# logic_board_Protorype_5_4_ver3.net
KiCad netlist of a schematic drawn in EAGLE
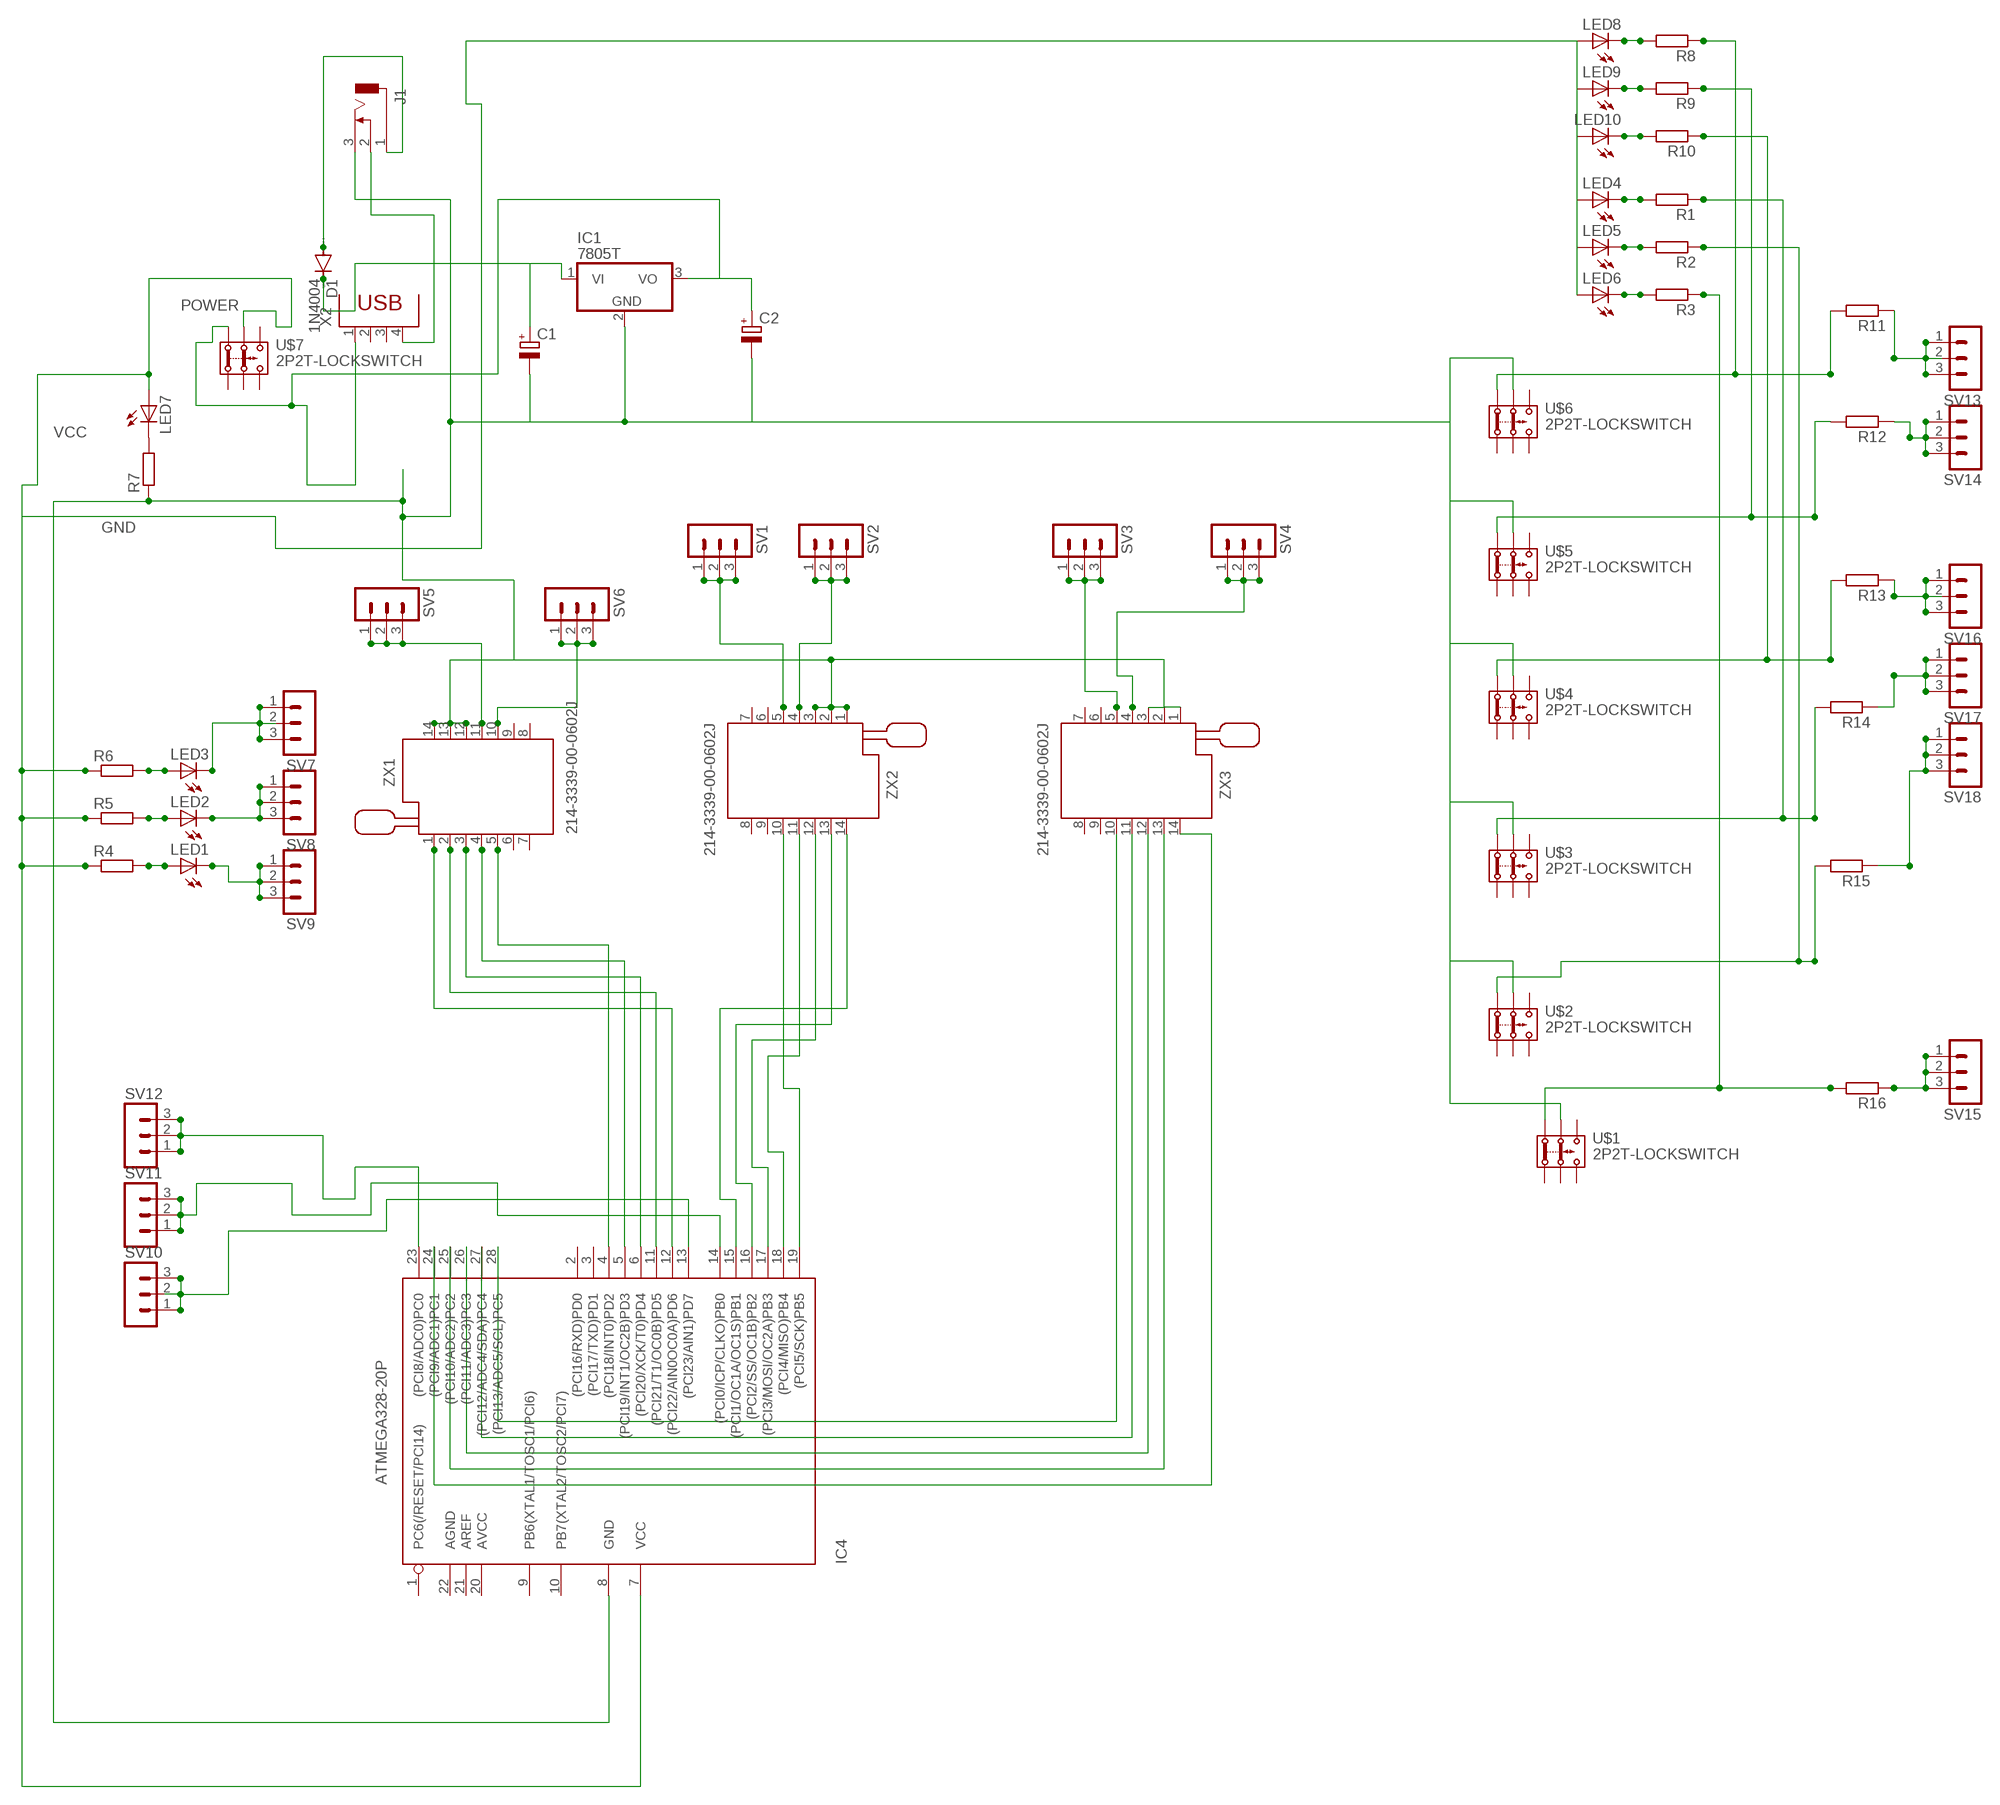
[diagram p0: schematic, sheet 1]

(export (version "E")
  (design (tool "Eeschema 10.0.6"))
  (components
    (comp (ref "C1")
      (value "CPOL-EUE2.5-6")
      (footprint "eagle-import:E2,5-6")
      (libsource (lib "eagle-import") (part "CPOL-EUE2.5-6"))
    )
    (comp (ref "C2")
      (value "CPOL-EUE2.5-6")
      (footprint "eagle-import:E2,5-6")
      (libsource (lib "eagle-import") (part "CPOL-EUE2.5-6"))
    )
    (comp (ref "D1")
      (value "1N4004")
      (footprint "eagle-import:DO41-10")
      (libsource (lib "eagle-import") (part "1N4004"))
    )
    (comp (ref "IC1")
      (value "7805T")
      (footprint "eagle-import:TO220H")
      (libsource (lib "eagle-import") (part "78T05"))
    )
    (comp (ref "IC4")
      (value "ATMEGA328-20P")
      (footprint "eagle-import:DIL28-3")
      (libsource (lib "eagle-import") (part "ATMEGA328P-20"))
    )
    (comp (ref "J1")
      (value "DCJ0303")
      (footprint "eagle-import:DCJ0303")
      (libsource (lib "eagle-import") (part "DCJ0303"))
    )
    (comp (ref "LED1")
      (value "LEDLED5MM-CHANDIMA")
      (footprint "eagle-import:LED5MM-CHANDIMA")
      (libsource (lib "eagle-import") (part "LEDLED5MM-CHANDIMA"))
    )
    (comp (ref "LED2")
      (value "LEDLED5MM-CHANDIMA")
      (footprint "eagle-import:LED5MM-CHANDIMA")
      (libsource (lib "eagle-import") (part "LEDLED5MM-CHANDIMA"))
    )
    (comp (ref "LED3")
      (value "LEDLED5MM-CHANDIMA")
      (footprint "eagle-import:LED5MM-CHANDIMA")
      (libsource (lib "eagle-import") (part "LEDLED5MM-CHANDIMA"))
    )
    (comp (ref "LED4")
      (value "LEDLED5MM-CHANDIMA")
      (footprint "eagle-import:LED5MM-CHANDIMA")
      (libsource (lib "eagle-import") (part "LEDLED5MM-CHANDIMA"))
    )
    (comp (ref "LED5")
      (value "LEDLED5MM-CHANDIMA")
      (footprint "eagle-import:LED5MM-CHANDIMA")
      (libsource (lib "eagle-import") (part "LEDLED5MM-CHANDIMA"))
    )
    (comp (ref "LED6")
      (value "LEDLED5MM-CHANDIMA")
      (footprint "eagle-import:LED5MM-CHANDIMA")
      (libsource (lib "eagle-import") (part "LEDLED5MM-CHANDIMA"))
    )
    (comp (ref "LED7")
      (value "LEDLED5MM-CHANDIMA")
      (footprint "eagle-import:LED5MM-CHANDIMA")
      (libsource (lib "eagle-import") (part "LEDLED5MM-CHANDIMA"))
    )
    (comp (ref "LED8")
      (value "LEDLED5MM-CHANDIMA")
      (footprint "eagle-import:LED5MM-CHANDIMA")
      (libsource (lib "eagle-import") (part "LEDLED5MM-CHANDIMA"))
    )
    (comp (ref "LED9")
      (value "LEDLED5MM-CHANDIMA")
      (footprint "eagle-import:LED5MM-CHANDIMA")
      (libsource (lib "eagle-import") (part "LEDLED5MM-CHANDIMA"))
    )
    (comp (ref "LED10")
      (value "LEDLED5MM-CHANDIMA")
      (footprint "eagle-import:LED5MM-CHANDIMA")
      (libsource (lib "eagle-import") (part "LEDLED5MM-CHANDIMA"))
    )
    (comp (ref "R1")
      (value "R-EU_0207/10_CHANDIMA")
      (footprint "eagle-import:0207_10_CHANDIMA")
      (libsource (lib "eagle-import") (part "R-EU_0207/10_CHANDIMA"))
    )
    (comp (ref "R2")
      (value "R-EU_0207/10_CHANDIMA")
      (footprint "eagle-import:0207_10_CHANDIMA")
      (libsource (lib "eagle-import") (part "R-EU_0207/10_CHANDIMA"))
    )
    (comp (ref "R3")
      (value "R-EU_0207/10_CHANDIMA")
      (footprint "eagle-import:0207_10_CHANDIMA")
      (libsource (lib "eagle-import") (part "R-EU_0207/10_CHANDIMA"))
    )
    (comp (ref "R4")
      (value "R-EU_0207/10_CHANDIMA")
      (footprint "eagle-import:0207_10_CHANDIMA")
      (libsource (lib "eagle-import") (part "R-EU_0207/10_CHANDIMA"))
    )
    (comp (ref "R5")
      (value "R-EU_0207/10_CHANDIMA")
      (footprint "eagle-import:0207_10_CHANDIMA")
      (libsource (lib "eagle-import") (part "R-EU_0207/10_CHANDIMA"))
    )
    (comp (ref "R6")
      (value "R-EU_0207/10_CHANDIMA")
      (footprint "eagle-import:0207_10_CHANDIMA")
      (libsource (lib "eagle-import") (part "R-EU_0207/10_CHANDIMA"))
    )
    (comp (ref "R7")
      (value "R-EU_0207/10_CHANDIMA")
      (footprint "eagle-import:0207_10_CHANDIMA")
      (libsource (lib "eagle-import") (part "R-EU_0207/10_CHANDIMA"))
    )
    (comp (ref "R8")
      (value "R-EU_0207/10_CHANDIMA")
      (footprint "eagle-import:0207_10_CHANDIMA")
      (libsource (lib "eagle-import") (part "R-EU_0207/10_CHANDIMA"))
    )
    (comp (ref "R9")
      (value "R-EU_0207/10_CHANDIMA")
      (footprint "eagle-import:0207_10_CHANDIMA")
      (libsource (lib "eagle-import") (part "R-EU_0207/10_CHANDIMA"))
    )
    (comp (ref "R10")
      (value "R-EU_0207/10_CHANDIMA")
      (footprint "eagle-import:0207_10_CHANDIMA")
      (libsource (lib "eagle-import") (part "R-EU_0207/10_CHANDIMA"))
    )
    (comp (ref "R11")
      (value "R-EU_0207/10_CHANDIMA")
      (footprint "eagle-import:0207_10_CHANDIMA")
      (libsource (lib "eagle-import") (part "R-EU_0207/10_CHANDIMA"))
    )
    (comp (ref "R12")
      (value "R-EU_0207/10_CHANDIMA")
      (footprint "eagle-import:0207_10_CHANDIMA")
      (libsource (lib "eagle-import") (part "R-EU_0207/10_CHANDIMA"))
    )
    (comp (ref "R13")
      (value "R-EU_0207/10_CHANDIMA")
      (footprint "eagle-import:0207_10_CHANDIMA")
      (libsource (lib "eagle-import") (part "R-EU_0207/10_CHANDIMA"))
    )
    (comp (ref "R14")
      (value "R-EU_0207/10_CHANDIMA")
      (footprint "eagle-import:0207_10_CHANDIMA")
      (libsource (lib "eagle-import") (part "R-EU_0207/10_CHANDIMA"))
    )
    (comp (ref "R15")
      (value "R-EU_0207/10_CHANDIMA")
      (footprint "eagle-import:0207_10_CHANDIMA")
      (libsource (lib "eagle-import") (part "R-EU_0207/10_CHANDIMA"))
    )
    (comp (ref "R16")
      (value "R-EU_0207/10_CHANDIMA")
      (footprint "eagle-import:0207_10_CHANDIMA")
      (libsource (lib "eagle-import") (part "R-EU_0207/10_CHANDIMA"))
    )
    (comp (ref "SV1")
      (value "MA03-1")
      (footprint "eagle-import:MA03-1")
      (libsource (lib "eagle-import") (part "MA03-1"))
    )
    (comp (ref "SV2")
      (value "MA03-1")
      (footprint "eagle-import:MA03-1")
      (libsource (lib "eagle-import") (part "MA03-1"))
    )
    (comp (ref "SV3")
      (value "MA03-1")
      (footprint "eagle-import:MA03-1")
      (libsource (lib "eagle-import") (part "MA03-1"))
    )
    (comp (ref "SV4")
      (value "MA03-1")
      (footprint "eagle-import:MA03-1")
      (libsource (lib "eagle-import") (part "MA03-1"))
    )
    (comp (ref "SV5")
      (value "MA03-1")
      (footprint "eagle-import:MA03-1")
      (libsource (lib "eagle-import") (part "MA03-1"))
    )
    (comp (ref "SV6")
      (value "MA03-1")
      (footprint "eagle-import:MA03-1")
      (libsource (lib "eagle-import") (part "MA03-1"))
    )
    (comp (ref "SV7")
      (value "MA03-1")
      (footprint "eagle-import:MA03-1")
      (libsource (lib "eagle-import") (part "MA03-1"))
    )
    (comp (ref "SV8")
      (value "MA03-1")
      (footprint "eagle-import:MA03-1")
      (libsource (lib "eagle-import") (part "MA03-1"))
    )
    (comp (ref "SV9")
      (value "MA03-1")
      (footprint "eagle-import:MA03-1")
      (libsource (lib "eagle-import") (part "MA03-1"))
    )
    (comp (ref "SV10")
      (value "MA03-1")
      (footprint "eagle-import:MA03-1")
      (libsource (lib "eagle-import") (part "MA03-1"))
    )
    (comp (ref "SV11")
      (value "MA03-1")
      (footprint "eagle-import:MA03-1")
      (libsource (lib "eagle-import") (part "MA03-1"))
    )
    (comp (ref "SV12")
      (value "MA03-1")
      (footprint "eagle-import:MA03-1")
      (libsource (lib "eagle-import") (part "MA03-1"))
    )
    (comp (ref "SV13")
      (value "MA03-1")
      (footprint "eagle-import:MA03-1")
      (libsource (lib "eagle-import") (part "MA03-1"))
    )
    (comp (ref "SV14")
      (value "MA03-1")
      (footprint "eagle-import:MA03-1")
      (libsource (lib "eagle-import") (part "MA03-1"))
    )
    (comp (ref "SV15")
      (value "MA03-1")
      (footprint "eagle-import:MA03-1")
      (libsource (lib "eagle-import") (part "MA03-1"))
    )
    (comp (ref "SV16")
      (value "MA03-1")
      (footprint "eagle-import:MA03-1")
      (libsource (lib "eagle-import") (part "MA03-1"))
    )
    (comp (ref "SV17")
      (value "MA03-1")
      (footprint "eagle-import:MA03-1")
      (libsource (lib "eagle-import") (part "MA03-1"))
    )
    (comp (ref "SV18")
      (value "MA03-1")
      (footprint "eagle-import:MA03-1")
      (libsource (lib "eagle-import") (part "MA03-1"))
    )
    (comp (ref "U$1")
      (value "2P2T-LOCKSWITCH")
      (footprint "eagle-import:2P2T-LOCKSWITCH")
      (libsource (lib "eagle-import") (part "2P2T-LOCKSWITCH"))
    )
    (comp (ref "U$2")
      (value "2P2T-LOCKSWITCH")
      (footprint "eagle-import:2P2T-LOCKSWITCH")
      (libsource (lib "eagle-import") (part "2P2T-LOCKSWITCH"))
    )
    (comp (ref "U$3")
      (value "2P2T-LOCKSWITCH")
      (footprint "eagle-import:2P2T-LOCKSWITCH")
      (libsource (lib "eagle-import") (part "2P2T-LOCKSWITCH"))
    )
    (comp (ref "U$4")
      (value "2P2T-LOCKSWITCH")
      (footprint "eagle-import:2P2T-LOCKSWITCH")
      (libsource (lib "eagle-import") (part "2P2T-LOCKSWITCH"))
    )
    (comp (ref "U$5")
      (value "2P2T-LOCKSWITCH")
      (footprint "eagle-import:2P2T-LOCKSWITCH")
      (libsource (lib "eagle-import") (part "2P2T-LOCKSWITCH"))
    )
    (comp (ref "U$6")
      (value "2P2T-LOCKSWITCH")
      (footprint "eagle-import:2P2T-LOCKSWITCH")
      (libsource (lib "eagle-import") (part "2P2T-LOCKSWITCH"))
    )
    (comp (ref "U$7")
      (value "2P2T-LOCKSWITCH")
      (footprint "eagle-import:2P2T-LOCKSWITCH")
      (libsource (lib "eagle-import") (part "2P2T-LOCKSWITCH"))
    )
    (comp (ref "X2")
      (value "PN61729")
      (footprint "eagle-import:PN61729")
      (libsource (lib "eagle-import") (part "PN61729"))
    )
    (comp (ref "ZX1")
      (value "214-3339-00-0602J")
      (footprint "eagle-import:214-3339-00-0602J")
      (fields (field (name "MF") "3M"))
      (libsource (lib "eagle-import") (part "214-3339-00-0602J"))
    )
    (comp (ref "ZX2")
      (value "214-3339-00-0602J")
      (footprint "eagle-import:214-3339-00-0602J")
      (fields (field (name "MF") "3M"))
      (libsource (lib "eagle-import") (part "214-3339-00-0602J"))
    )
    (comp (ref "ZX3")
      (value "214-3339-00-0602J")
      (footprint "eagle-import:214-3339-00-0602J")
      (fields (field (name "MF") "3M"))
      (libsource (lib "eagle-import") (part "214-3339-00-0602J"))
    )
  )
  (nets
    (net (code "1") (name "/GND") (class "Default")
      (node (ref "C1") (pin "-") (pinfunction "-_-") (pintype "passive"))
      (node (ref "C2") (pin "-") (pinfunction "-_-") (pintype "passive"))
      (node (ref "IC1") (pin "2") (pinfunction "GND_2") (pintype "passive"))
      (node (ref "IC4") (pin "8") (pinfunction "GND_8") (pintype "bidirectional"))
      (node (ref "J1") (pin "3") (pinfunction "3_3") (pintype "passive"))
      (node (ref "R7") (pin "1") (pinfunction "1_1") (pintype "passive"))
      (node (ref "U$1") (pin "2.1") (pinfunction "2.1_2.1") (pintype "passive"))
      (node (ref "U$2") (pin "2.1") (pinfunction "2.1_2.1") (pintype "passive"))
      (node (ref "U$3") (pin "2.1") (pinfunction "2.1_2.1") (pintype "passive"))
      (node (ref "U$4") (pin "2.1") (pinfunction "2.1_2.1") (pintype "passive"))
      (node (ref "U$5") (pin "2.1") (pinfunction "2.1_2.1") (pintype "passive"))
      (node (ref "U$6") (pin "2.1") (pinfunction "2.1_2.1") (pintype "passive"))
      (node (ref "ZX1") (pin "12") (pinfunction "12_12") (pintype "passive"))
      (node (ref "ZX1") (pin "13") (pinfunction "13_13") (pintype "passive"))
      (node (ref "ZX1") (pin "14") (pinfunction "14_14") (pintype "passive"))
      (node (ref "ZX2") (pin "1") (pinfunction "1_1") (pintype "passive"))
      (node (ref "ZX2") (pin "2") (pinfunction "2_2") (pintype "passive"))
      (node (ref "ZX2") (pin "3") (pinfunction "3_3") (pintype "passive"))
      (node (ref "ZX3") (pin "1") (pinfunction "1_1") (pintype "passive"))
      (node (ref "ZX3") (pin "2") (pinfunction "2_2") (pintype "passive"))
      (node (ref "ZX3") (pin "3") (pinfunction "3_3") (pintype "passive"))
    )
    (net (code "2") (name "/POWER") (class "Default")
      (node (ref "C2") (pin "+") (pinfunction "+_+") (pintype "passive"))
      (node (ref "IC1") (pin "3") (pinfunction "VO_3") (pintype "passive"))
      (node (ref "U$7") (pin "1.1") (pinfunction "1.1_1.1") (pintype "passive"))
      (node (ref "X2") (pin "1") (pinfunction "1_1") (pintype "passive"))
    )
    (net (code "3") (name "/VCC") (class "Default")
      (node (ref "IC4") (pin "7") (pinfunction "VCC_7") (pintype "bidirectional"))
      (node (ref "LED10") (pin "A") (pinfunction "A_A") (pintype "passive"))
      (node (ref "LED4") (pin "A") (pinfunction "A_A") (pintype "passive"))
      (node (ref "LED5") (pin "A") (pinfunction "A_A") (pintype "passive"))
      (node (ref "LED6") (pin "A") (pinfunction "A_A") (pintype "passive"))
      (node (ref "LED7") (pin "A") (pinfunction "A_A") (pintype "passive"))
      (node (ref "LED8") (pin "A") (pinfunction "A_A") (pintype "passive"))
      (node (ref "LED9") (pin "A") (pinfunction "A_A") (pintype "passive"))
      (node (ref "R4") (pin "1") (pinfunction "1_1") (pintype "passive"))
      (node (ref "R5") (pin "1") (pinfunction "1_1") (pintype "passive"))
      (node (ref "R6") (pin "1") (pinfunction "1_1") (pintype "passive"))
      (node (ref "U$7") (pin "2.1") (pinfunction "2.1_2.1") (pintype "passive"))
    )
    (net (code "4") (name "Net-(D1-PadA)") (class "Default")
      (node (ref "D1") (pin "A") (pinfunction "A_A") (pintype "passive"))
      (node (ref "J1") (pin "1") (pinfunction "1_1") (pintype "passive"))
    )
    (net (code "5") (name "Net-(IC1-VI)") (class "Default")
      (node (ref "C1") (pin "+") (pinfunction "+_+") (pintype "passive"))
      (node (ref "D1") (pin "C") (pinfunction "C_C") (pintype "passive"))
      (node (ref "IC1") (pin "1") (pinfunction "VI_1") (pintype "input"))
    )
    (net (code "6") (name "Net-(IC4-(PCI0{slash}ICP{slash}CLKO)PB0)") (class "Default")
      (node (ref "IC4") (pin "14") (pinfunction "(PCI0/ICP/CLKO)PB0_14") (pintype "bidirectional"))
      (node (ref "SV11") (pin "1") (pinfunction "1_1") (pintype "passive"))
      (node (ref "SV11") (pin "2") (pinfunction "2_2") (pintype "passive"))
      (node (ref "SV11") (pin "3") (pinfunction "3_3") (pintype "passive"))
    )
    (net (code "7") (name "Net-(IC4-(PCI1{slash}OC1A{slash}OC1S)PB1)") (class "Default")
      (node (ref "IC4") (pin "15") (pinfunction "(PCI1/OC1A/OC1S)PB1_15") (pintype "bidirectional"))
      (node (ref "ZX2") (pin "14") (pinfunction "14_14") (pintype "passive"))
    )
    (net (code "8") (name "Net-(IC4-(PCI2{slash}SS{slash}OC1B)PB2)") (class "Default")
      (node (ref "IC4") (pin "16") (pinfunction "(PCI2/SS/OC1B)PB2_16") (pintype "bidirectional"))
      (node (ref "ZX2") (pin "13") (pinfunction "13_13") (pintype "passive"))
    )
    (net (code "9") (name "Net-(IC4-(PCI3{slash}MOSI{slash}OC2A)PB3)") (class "Default")
      (node (ref "IC4") (pin "17") (pinfunction "(PCI3/MOSI/OC2A)PB3_17") (pintype "bidirectional"))
      (node (ref "ZX2") (pin "12") (pinfunction "12_12") (pintype "passive"))
    )
    (net (code "10") (name "Net-(IC4-(PCI4{slash}MISO)PB4)") (class "Default")
      (node (ref "IC4") (pin "18") (pinfunction "(PCI4/MISO)PB4_18") (pintype "bidirectional"))
      (node (ref "ZX2") (pin "11") (pinfunction "11_11") (pintype "passive"))
    )
    (net (code "11") (name "Net-(IC4-(PCI5{slash}SCK)PB5)") (class "Default")
      (node (ref "IC4") (pin "19") (pinfunction "(PCI5/SCK)PB5_19") (pintype "bidirectional"))
      (node (ref "ZX2") (pin "10") (pinfunction "10_10") (pintype "passive"))
    )
    (net (code "12") (name "Net-(IC4-(PCI8{slash}ADC0)PC0)") (class "Default")
      (node (ref "IC4") (pin "23") (pinfunction "(PCI8/ADC0)PC0_23") (pintype "bidirectional"))
      (node (ref "SV12") (pin "1") (pinfunction "1_1") (pintype "passive"))
      (node (ref "SV12") (pin "2") (pinfunction "2_2") (pintype "passive"))
      (node (ref "SV12") (pin "3") (pinfunction "3_3") (pintype "passive"))
    )
    (net (code "13") (name "Net-(IC4-(PCI9{slash}ADC1)PC1)") (class "Default")
      (node (ref "IC4") (pin "24") (pinfunction "(PCI9/ADC1)PC1_24") (pintype "bidirectional"))
      (node (ref "ZX3") (pin "14") (pinfunction "14_14") (pintype "passive"))
    )
    (net (code "14") (name "Net-(IC4-(PCI10{slash}ADC2)PC2)") (class "Default")
      (node (ref "IC4") (pin "25") (pinfunction "(PCI10/ADC2)PC2_25") (pintype "bidirectional"))
      (node (ref "ZX3") (pin "13") (pinfunction "13_13") (pintype "passive"))
    )
    (net (code "15") (name "Net-(IC4-(PCI11{slash}ADC3)PC3)") (class "Default")
      (node (ref "IC4") (pin "26") (pinfunction "(PCI11/ADC3)PC3_26") (pintype "bidirectional"))
      (node (ref "ZX3") (pin "12") (pinfunction "12_12") (pintype "passive"))
    )
    (net (code "16") (name "Net-(IC4-(PCI12{slash}ADC4{slash}SDA)PC4)") (class "Default")
      (node (ref "IC4") (pin "27") (pinfunction "(PCI12/ADC4/SDA)PC4_27") (pintype "bidirectional"))
      (node (ref "ZX3") (pin "11") (pinfunction "11_11") (pintype "passive"))
    )
    (net (code "17") (name "Net-(IC4-(PCI13{slash}ADC5{slash}SCL)PC5)") (class "Default")
      (node (ref "IC4") (pin "28") (pinfunction "(PCI13/ADC5/SCL)PC5_28") (pintype "bidirectional"))
      (node (ref "ZX3") (pin "10") (pinfunction "10_10") (pintype "passive"))
    )
    (net (code "18") (name "Net-(IC4-(PCI18{slash}INT0)PD2)") (class "Default")
      (node (ref "IC4") (pin "4") (pinfunction "(PCI18/INT0)PD2_4") (pintype "bidirectional"))
      (node (ref "ZX1") (pin "5") (pinfunction "5_5") (pintype "passive"))
    )
    (net (code "19") (name "Net-(IC4-(PCI19{slash}INT1{slash}OC2B)PD3)") (class "Default")
      (node (ref "IC4") (pin "5") (pinfunction "(PCI19/INT1/OC2B)PD3_5") (pintype "bidirectional"))
      (node (ref "ZX1") (pin "4") (pinfunction "4_4") (pintype "passive"))
    )
    (net (code "20") (name "Net-(IC4-(PCI20{slash}XCK{slash}T0)PD4)") (class "Default")
      (node (ref "IC4") (pin "6") (pinfunction "(PCI20/XCK/T0)PD4_6") (pintype "bidirectional"))
      (node (ref "ZX1") (pin "3") (pinfunction "3_3") (pintype "passive"))
    )
    (net (code "21") (name "Net-(IC4-(PCI21{slash}T1{slash}OC0B)PD5)") (class "Default")
      (node (ref "IC4") (pin "11") (pinfunction "(PCI21/T1/OC0B)PD5_11") (pintype "bidirectional"))
      (node (ref "ZX1") (pin "2") (pinfunction "2_2") (pintype "passive"))
    )
    (net (code "22") (name "Net-(IC4-(PCI22{slash}AIN0OC0A)PD6)") (class "Default")
      (node (ref "IC4") (pin "12") (pinfunction "(PCI22/AIN0OC0A)PD6_12") (pintype "bidirectional"))
      (node (ref "ZX1") (pin "1") (pinfunction "1_1") (pintype "passive"))
    )
    (net (code "23") (name "Net-(IC4-(PCI23{slash}AIN1)PD7)") (class "Default")
      (node (ref "IC4") (pin "13") (pinfunction "(PCI23/AIN1)PD7_13") (pintype "bidirectional"))
      (node (ref "SV10") (pin "1") (pinfunction "1_1") (pintype "passive"))
      (node (ref "SV10") (pin "2") (pinfunction "2_2") (pintype "passive"))
      (node (ref "SV10") (pin "3") (pinfunction "3_3") (pintype "passive"))
    )
    (net (code "24") (name "Net-(J1-Pad2)") (class "Default")
      (node (ref "J1") (pin "2") (pinfunction "2_2") (pintype "passive"))
      (node (ref "X2") (pin "4") (pinfunction "4_4") (pintype "passive"))
    )
    (net (code "25") (name "Net-(LED1-C)") (class "Default")
      (node (ref "LED1") (pin "K") (pinfunction "C_K") (pintype "passive"))
      (node (ref "SV9") (pin "1") (pinfunction "1_1") (pintype "passive"))
      (node (ref "SV9") (pin "2") (pinfunction "2_2") (pintype "passive"))
      (node (ref "SV9") (pin "3") (pinfunction "3_3") (pintype "passive"))
    )
    (net (code "26") (name "Net-(LED1-PadA)") (class "Default")
      (node (ref "LED1") (pin "A") (pinfunction "A_A") (pintype "passive"))
      (node (ref "R4") (pin "2") (pinfunction "2_2") (pintype "passive"))
    )
    (net (code "27") (name "Net-(LED2-C)") (class "Default")
      (node (ref "LED2") (pin "K") (pinfunction "C_K") (pintype "passive"))
      (node (ref "SV8") (pin "1") (pinfunction "1_1") (pintype "passive"))
      (node (ref "SV8") (pin "2") (pinfunction "2_2") (pintype "passive"))
      (node (ref "SV8") (pin "3") (pinfunction "3_3") (pintype "passive"))
    )
    (net (code "28") (name "Net-(LED2-PadA)") (class "Default")
      (node (ref "LED2") (pin "A") (pinfunction "A_A") (pintype "passive"))
      (node (ref "R5") (pin "2") (pinfunction "2_2") (pintype "passive"))
    )
    (net (code "29") (name "Net-(LED3-C)") (class "Default")
      (node (ref "LED3") (pin "K") (pinfunction "C_K") (pintype "passive"))
      (node (ref "SV7") (pin "1") (pinfunction "1_1") (pintype "passive"))
      (node (ref "SV7") (pin "2") (pinfunction "2_2") (pintype "passive"))
      (node (ref "SV7") (pin "3") (pinfunction "3_3") (pintype "passive"))
    )
    (net (code "30") (name "Net-(LED3-PadA)") (class "Default")
      (node (ref "LED3") (pin "A") (pinfunction "A_A") (pintype "passive"))
      (node (ref "R6") (pin "2") (pinfunction "2_2") (pintype "passive"))
    )
    (net (code "31") (name "Net-(LED4-C)") (class "Default")
      (node (ref "LED4") (pin "K") (pinfunction "C_K") (pintype "passive"))
      (node (ref "R1") (pin "2") (pinfunction "2_2") (pintype "passive"))
    )
    (net (code "32") (name "Net-(LED5-C)") (class "Default")
      (node (ref "LED5") (pin "K") (pinfunction "C_K") (pintype "passive"))
      (node (ref "R2") (pin "2") (pinfunction "2_2") (pintype "passive"))
    )
    (net (code "33") (name "Net-(LED6-C)") (class "Default")
      (node (ref "LED6") (pin "K") (pinfunction "C_K") (pintype "passive"))
      (node (ref "R3") (pin "2") (pinfunction "2_2") (pintype "passive"))
    )
    (net (code "34") (name "Net-(LED7-C)") (class "Default")
      (node (ref "LED7") (pin "K") (pinfunction "C_K") (pintype "passive"))
      (node (ref "R7") (pin "2") (pinfunction "2_2") (pintype "passive"))
    )
    (net (code "35") (name "Net-(LED8-C)") (class "Default")
      (node (ref "LED8") (pin "K") (pinfunction "C_K") (pintype "passive"))
      (node (ref "R8") (pin "2") (pinfunction "2_2") (pintype "passive"))
    )
    (net (code "36") (name "Net-(LED9-C)") (class "Default")
      (node (ref "LED9") (pin "K") (pinfunction "C_K") (pintype "passive"))
      (node (ref "R9") (pin "2") (pinfunction "2_2") (pintype "passive"))
    )
    (net (code "37") (name "Net-(LED10-C)") (class "Default")
      (node (ref "LED10") (pin "K") (pinfunction "C_K") (pintype "passive"))
      (node (ref "R10") (pin "2") (pinfunction "2_2") (pintype "passive"))
    )
    (net (code "38") (name "Net-(R1-Pad1)") (class "Default")
      (node (ref "R1") (pin "1") (pinfunction "1_1") (pintype "passive"))
      (node (ref "R14") (pin "2") (pinfunction "2_2") (pintype "passive"))
      (node (ref "U$3") (pin "1.1") (pinfunction "1.1_1.1") (pintype "passive"))
    )
    (net (code "39") (name "Net-(R10-Pad1)") (class "Default")
      (node (ref "R10") (pin "1") (pinfunction "1_1") (pintype "passive"))
      (node (ref "R13") (pin "2") (pinfunction "2_2") (pintype "passive"))
      (node (ref "U$4") (pin "1.1") (pinfunction "1.1_1.1") (pintype "passive"))
    )
    (net (code "40") (name "Net-(R11-Pad1)") (class "Default")
      (node (ref "R11") (pin "1") (pinfunction "1_1") (pintype "passive"))
      (node (ref "SV13") (pin "1") (pinfunction "1_1") (pintype "passive"))
      (node (ref "SV13") (pin "2") (pinfunction "2_2") (pintype "passive"))
      (node (ref "SV13") (pin "3") (pinfunction "3_3") (pintype "passive"))
    )
    (net (code "41") (name "Net-(R11-Pad2)") (class "Default")
      (node (ref "R11") (pin "2") (pinfunction "2_2") (pintype "passive"))
      (node (ref "R8") (pin "1") (pinfunction "1_1") (pintype "passive"))
      (node (ref "U$6") (pin "1.1") (pinfunction "1.1_1.1") (pintype "passive"))
    )
    (net (code "42") (name "Net-(R12-Pad1)") (class "Default")
      (node (ref "R12") (pin "1") (pinfunction "1_1") (pintype "passive"))
      (node (ref "SV14") (pin "1") (pinfunction "1_1") (pintype "passive"))
      (node (ref "SV14") (pin "2") (pinfunction "2_2") (pintype "passive"))
      (node (ref "SV14") (pin "3") (pinfunction "3_3") (pintype "passive"))
    )
    (net (code "43") (name "Net-(R12-Pad2)") (class "Default")
      (node (ref "R12") (pin "2") (pinfunction "2_2") (pintype "passive"))
      (node (ref "R9") (pin "1") (pinfunction "1_1") (pintype "passive"))
      (node (ref "U$5") (pin "1.1") (pinfunction "1.1_1.1") (pintype "passive"))
    )
    (net (code "44") (name "Net-(R13-Pad1)") (class "Default")
      (node (ref "R13") (pin "1") (pinfunction "1_1") (pintype "passive"))
      (node (ref "SV16") (pin "1") (pinfunction "1_1") (pintype "passive"))
      (node (ref "SV16") (pin "2") (pinfunction "2_2") (pintype "passive"))
      (node (ref "SV16") (pin "3") (pinfunction "3_3") (pintype "passive"))
    )
    (net (code "45") (name "Net-(R14-Pad1)") (class "Default")
      (node (ref "R14") (pin "1") (pinfunction "1_1") (pintype "passive"))
      (node (ref "SV17") (pin "1") (pinfunction "1_1") (pintype "passive"))
      (node (ref "SV17") (pin "2") (pinfunction "2_2") (pintype "passive"))
      (node (ref "SV17") (pin "3") (pinfunction "3_3") (pintype "passive"))
    )
    (net (code "46") (name "Net-(R15-Pad1)") (class "Default")
      (node (ref "R15") (pin "1") (pinfunction "1_1") (pintype "passive"))
      (node (ref "SV18") (pin "1") (pinfunction "1_1") (pintype "passive"))
      (node (ref "SV18") (pin "2") (pinfunction "2_2") (pintype "passive"))
      (node (ref "SV18") (pin "3") (pinfunction "3_3") (pintype "passive"))
    )
    (net (code "47") (name "Net-(R15-Pad2)") (class "Default")
      (node (ref "R15") (pin "2") (pinfunction "2_2") (pintype "passive"))
      (node (ref "R2") (pin "1") (pinfunction "1_1") (pintype "passive"))
      (node (ref "U$2") (pin "1.1") (pinfunction "1.1_1.1") (pintype "passive"))
    )
    (net (code "48") (name "Net-(R16-Pad1)") (class "Default")
      (node (ref "R16") (pin "1") (pinfunction "1_1") (pintype "passive"))
      (node (ref "SV15") (pin "1") (pinfunction "1_1") (pintype "passive"))
      (node (ref "SV15") (pin "2") (pinfunction "2_2") (pintype "passive"))
      (node (ref "SV15") (pin "3") (pinfunction "3_3") (pintype "passive"))
    )
    (net (code "49") (name "Net-(R16-Pad2)") (class "Default")
      (node (ref "R16") (pin "2") (pinfunction "2_2") (pintype "passive"))
      (node (ref "R3") (pin "1") (pinfunction "1_1") (pintype "passive"))
      (node (ref "U$1") (pin "1.1") (pinfunction "1.1_1.1") (pintype "passive"))
    )
    (net (code "50") (name "Net-(SV1-Pad1)") (class "Default")
      (node (ref "SV1") (pin "1") (pinfunction "1_1") (pintype "passive"))
      (node (ref "SV1") (pin "2") (pinfunction "2_2") (pintype "passive"))
      (node (ref "SV1") (pin "3") (pinfunction "3_3") (pintype "passive"))
      (node (ref "ZX2") (pin "5") (pinfunction "5_5") (pintype "passive"))
    )
    (net (code "51") (name "Net-(SV2-Pad1)") (class "Default")
      (node (ref "SV2") (pin "1") (pinfunction "1_1") (pintype "passive"))
      (node (ref "SV2") (pin "2") (pinfunction "2_2") (pintype "passive"))
      (node (ref "SV2") (pin "3") (pinfunction "3_3") (pintype "passive"))
      (node (ref "ZX2") (pin "4") (pinfunction "4_4") (pintype "passive"))
    )
    (net (code "52") (name "Net-(SV3-Pad1)") (class "Default")
      (node (ref "SV3") (pin "1") (pinfunction "1_1") (pintype "passive"))
      (node (ref "SV3") (pin "2") (pinfunction "2_2") (pintype "passive"))
      (node (ref "SV3") (pin "3") (pinfunction "3_3") (pintype "passive"))
      (node (ref "ZX3") (pin "5") (pinfunction "5_5") (pintype "passive"))
    )
    (net (code "53") (name "Net-(SV4-Pad1)") (class "Default")
      (node (ref "SV4") (pin "1") (pinfunction "1_1") (pintype "passive"))
      (node (ref "SV4") (pin "2") (pinfunction "2_2") (pintype "passive"))
      (node (ref "SV4") (pin "3") (pinfunction "3_3") (pintype "passive"))
      (node (ref "ZX3") (pin "4") (pinfunction "4_4") (pintype "passive"))
    )
    (net (code "54") (name "Net-(SV5-Pad1)") (class "Default")
      (node (ref "SV5") (pin "1") (pinfunction "1_1") (pintype "passive"))
      (node (ref "SV5") (pin "2") (pinfunction "2_2") (pintype "passive"))
      (node (ref "SV5") (pin "3") (pinfunction "3_3") (pintype "passive"))
      (node (ref "ZX1") (pin "11") (pinfunction "11_11") (pintype "passive"))
    )
    (net (code "55") (name "Net-(SV6-Pad1)") (class "Default")
      (node (ref "SV6") (pin "1") (pinfunction "1_1") (pintype "passive"))
      (node (ref "SV6") (pin "2") (pinfunction "2_2") (pintype "passive"))
      (node (ref "SV6") (pin "3") (pinfunction "3_3") (pintype "passive"))
      (node (ref "ZX1") (pin "10") (pinfunction "10_10") (pintype "passive"))
    )
    (net (code "56") (name "unconnected-(IC4-(PCI16{slash}RXD)PD0-Pad2)") (class "Default")
      (node (ref "IC4") (pin "2") (pinfunction "(PCI16/RXD)PD0_2") (pintype "bidirectional"))
    )
    (net (code "57") (name "unconnected-(IC4-(PCI17{slash}TXD)PD1-Pad3)") (class "Default")
      (node (ref "IC4") (pin "3") (pinfunction "(PCI17/TXD)PD1_3") (pintype "bidirectional"))
    )
    (net (code "58") (name "unconnected-(IC4-AGND-Pad22)") (class "Default")
      (node (ref "IC4") (pin "22") (pinfunction "AGND_22") (pintype "bidirectional"))
    )
    (net (code "59") (name "unconnected-(IC4-AREF-Pad21)") (class "Default")
      (node (ref "IC4") (pin "21") (pinfunction "AREF_21") (pintype "bidirectional"))
    )
    (net (code "60") (name "unconnected-(IC4-AVCC-Pad20)") (class "Default")
      (node (ref "IC4") (pin "20") (pinfunction "AVCC_20") (pintype "bidirectional"))
    )
    (net (code "61") (name "unconnected-(IC4-PB6(XTAL1{slash}TOSC1{slash}PCI6)-Pad9)") (class "Default")
      (node (ref "IC4") (pin "9") (pinfunction "PB6(XTAL1/TOSC1/PCI6)_9") (pintype "bidirectional"))
    )
    (net (code "62") (name "unconnected-(IC4-PB7(XTAL2{slash}TOSC2{slash}PCI7)-Pad10)") (class "Default")
      (node (ref "IC4") (pin "10") (pinfunction "PB7(XTAL2/TOSC2/PCI7)_10") (pintype "bidirectional"))
    )
    (net (code "63") (name "unconnected-(IC4-PC6({slash}RESET{slash}PCI14)-Pad1)") (class "Default")
      (node (ref "IC4") (pin "1") (pinfunction "PC6(/RESET/PCI14)_1") (pintype "bidirectional"))
    )
    (net (code "64") (name "unconnected-(U$1-Pad1.2)") (class "Default")
      (node (ref "U$1") (pin "1.2") (pinfunction "1.2_1.2") (pintype "passive"))
    )
    (net (code "65") (name "unconnected-(U$1-Pad2.2)") (class "Default")
      (node (ref "U$1") (pin "2.2") (pinfunction "2.2_2.2") (pintype "passive"))
    )
    (net (code "66") (name "unconnected-(U$1-Pad3.1)") (class "Default")
      (node (ref "U$1") (pin "3.1") (pinfunction "3.1_3.1") (pintype "passive"))
    )
    (net (code "67") (name "unconnected-(U$1-Pad3.2)") (class "Default")
      (node (ref "U$1") (pin "3.2") (pinfunction "3.2_3.2") (pintype "passive"))
    )
    (net (code "68") (name "unconnected-(U$2-Pad1.2)") (class "Default")
      (node (ref "U$2") (pin "1.2") (pinfunction "1.2_1.2") (pintype "passive"))
    )
    (net (code "69") (name "unconnected-(U$2-Pad2.2)") (class "Default")
      (node (ref "U$2") (pin "2.2") (pinfunction "2.2_2.2") (pintype "passive"))
    )
    (net (code "70") (name "unconnected-(U$2-Pad3.1)") (class "Default")
      (node (ref "U$2") (pin "3.1") (pinfunction "3.1_3.1") (pintype "passive"))
    )
    (net (code "71") (name "unconnected-(U$2-Pad3.2)") (class "Default")
      (node (ref "U$2") (pin "3.2") (pinfunction "3.2_3.2") (pintype "passive"))
    )
    (net (code "72") (name "unconnected-(U$3-Pad1.2)") (class "Default")
      (node (ref "U$3") (pin "1.2") (pinfunction "1.2_1.2") (pintype "passive"))
    )
    (net (code "73") (name "unconnected-(U$3-Pad2.2)") (class "Default")
      (node (ref "U$3") (pin "2.2") (pinfunction "2.2_2.2") (pintype "passive"))
    )
    (net (code "74") (name "unconnected-(U$3-Pad3.1)") (class "Default")
      (node (ref "U$3") (pin "3.1") (pinfunction "3.1_3.1") (pintype "passive"))
    )
    (net (code "75") (name "unconnected-(U$3-Pad3.2)") (class "Default")
      (node (ref "U$3") (pin "3.2") (pinfunction "3.2_3.2") (pintype "passive"))
    )
    (net (code "76") (name "unconnected-(U$4-Pad1.2)") (class "Default")
      (node (ref "U$4") (pin "1.2") (pinfunction "1.2_1.2") (pintype "passive"))
    )
    (net (code "77") (name "unconnected-(U$4-Pad2.2)") (class "Default")
      (node (ref "U$4") (pin "2.2") (pinfunction "2.2_2.2") (pintype "passive"))
    )
    (net (code "78") (name "unconnected-(U$4-Pad3.1)") (class "Default")
      (node (ref "U$4") (pin "3.1") (pinfunction "3.1_3.1") (pintype "passive"))
    )
    (net (code "79") (name "unconnected-(U$4-Pad3.2)") (class "Default")
      (node (ref "U$4") (pin "3.2") (pinfunction "3.2_3.2") (pintype "passive"))
    )
    (net (code "80") (name "unconnected-(U$5-Pad1.2)") (class "Default")
      (node (ref "U$5") (pin "1.2") (pinfunction "1.2_1.2") (pintype "passive"))
    )
    (net (code "81") (name "unconnected-(U$5-Pad2.2)") (class "Default")
      (node (ref "U$5") (pin "2.2") (pinfunction "2.2_2.2") (pintype "passive"))
    )
    (net (code "82") (name "unconnected-(U$5-Pad3.1)") (class "Default")
      (node (ref "U$5") (pin "3.1") (pinfunction "3.1_3.1") (pintype "passive"))
    )
    (net (code "83") (name "unconnected-(U$5-Pad3.2)") (class "Default")
      (node (ref "U$5") (pin "3.2") (pinfunction "3.2_3.2") (pintype "passive"))
    )
    (net (code "84") (name "unconnected-(U$6-Pad1.2)") (class "Default")
      (node (ref "U$6") (pin "1.2") (pinfunction "1.2_1.2") (pintype "passive"))
    )
    (net (code "85") (name "unconnected-(U$6-Pad2.2)") (class "Default")
      (node (ref "U$6") (pin "2.2") (pinfunction "2.2_2.2") (pintype "passive"))
    )
    (net (code "86") (name "unconnected-(U$6-Pad3.1)") (class "Default")
      (node (ref "U$6") (pin "3.1") (pinfunction "3.1_3.1") (pintype "passive"))
    )
    (net (code "87") (name "unconnected-(U$6-Pad3.2)") (class "Default")
      (node (ref "U$6") (pin "3.2") (pinfunction "3.2_3.2") (pintype "passive"))
    )
    (net (code "88") (name "unconnected-(U$7-Pad1.2)") (class "Default")
      (node (ref "U$7") (pin "1.2") (pinfunction "1.2_1.2") (pintype "passive"))
    )
    (net (code "89") (name "unconnected-(U$7-Pad2.2)") (class "Default")
      (node (ref "U$7") (pin "2.2") (pinfunction "2.2_2.2") (pintype "passive"))
    )
    (net (code "90") (name "unconnected-(U$7-Pad3.1)") (class "Default")
      (node (ref "U$7") (pin "3.1") (pinfunction "3.1_3.1") (pintype "passive"))
    )
    (net (code "91") (name "unconnected-(U$7-Pad3.2)") (class "Default")
      (node (ref "U$7") (pin "3.2") (pinfunction "3.2_3.2") (pintype "passive"))
    )
    (net (code "92") (name "unconnected-(X2-Pad2)") (class "Default")
      (node (ref "X2") (pin "2") (pinfunction "2_2") (pintype "passive"))
    )
    (net (code "93") (name "unconnected-(X2-Pad3)") (class "Default")
      (node (ref "X2") (pin "3") (pinfunction "3_3") (pintype "passive"))
    )
    (net (code "94") (name "unconnected-(ZX1-Pad6)") (class "Default")
      (node (ref "ZX1") (pin "6") (pinfunction "6_6") (pintype "passive"))
    )
    (net (code "95") (name "unconnected-(ZX1-Pad7)") (class "Default")
      (node (ref "ZX1") (pin "7") (pinfunction "7_7") (pintype "passive"))
    )
    (net (code "96") (name "unconnected-(ZX1-Pad8)") (class "Default")
      (node (ref "ZX1") (pin "8") (pinfunction "8_8") (pintype "passive"))
    )
    (net (code "97") (name "unconnected-(ZX1-Pad9)") (class "Default")
      (node (ref "ZX1") (pin "9") (pinfunction "9_9") (pintype "passive"))
    )
    (net (code "98") (name "unconnected-(ZX2-Pad6)") (class "Default")
      (node (ref "ZX2") (pin "6") (pinfunction "6_6") (pintype "passive"))
    )
    (net (code "99") (name "unconnected-(ZX2-Pad7)") (class "Default")
      (node (ref "ZX2") (pin "7") (pinfunction "7_7") (pintype "passive"))
    )
    (net (code "100") (name "unconnected-(ZX2-Pad8)") (class "Default")
      (node (ref "ZX2") (pin "8") (pinfunction "8_8") (pintype "passive"))
    )
    (net (code "101") (name "unconnected-(ZX2-Pad9)") (class "Default")
      (node (ref "ZX2") (pin "9") (pinfunction "9_9") (pintype "passive"))
    )
    (net (code "102") (name "unconnected-(ZX3-Pad6)") (class "Default")
      (node (ref "ZX3") (pin "6") (pinfunction "6_6") (pintype "passive"))
    )
    (net (code "103") (name "unconnected-(ZX3-Pad7)") (class "Default")
      (node (ref "ZX3") (pin "7") (pinfunction "7_7") (pintype "passive"))
    )
    (net (code "104") (name "unconnected-(ZX3-Pad8)") (class "Default")
      (node (ref "ZX3") (pin "8") (pinfunction "8_8") (pintype "passive"))
    )
    (net (code "105") (name "unconnected-(ZX3-Pad9)") (class "Default")
      (node (ref "ZX3") (pin "9") (pinfunction "9_9") (pintype "passive"))
    )
  )
)
